# LowerPlumbingBayBoardSchematic.net
KiCad netlist of a schematic drawn in Altium Designer
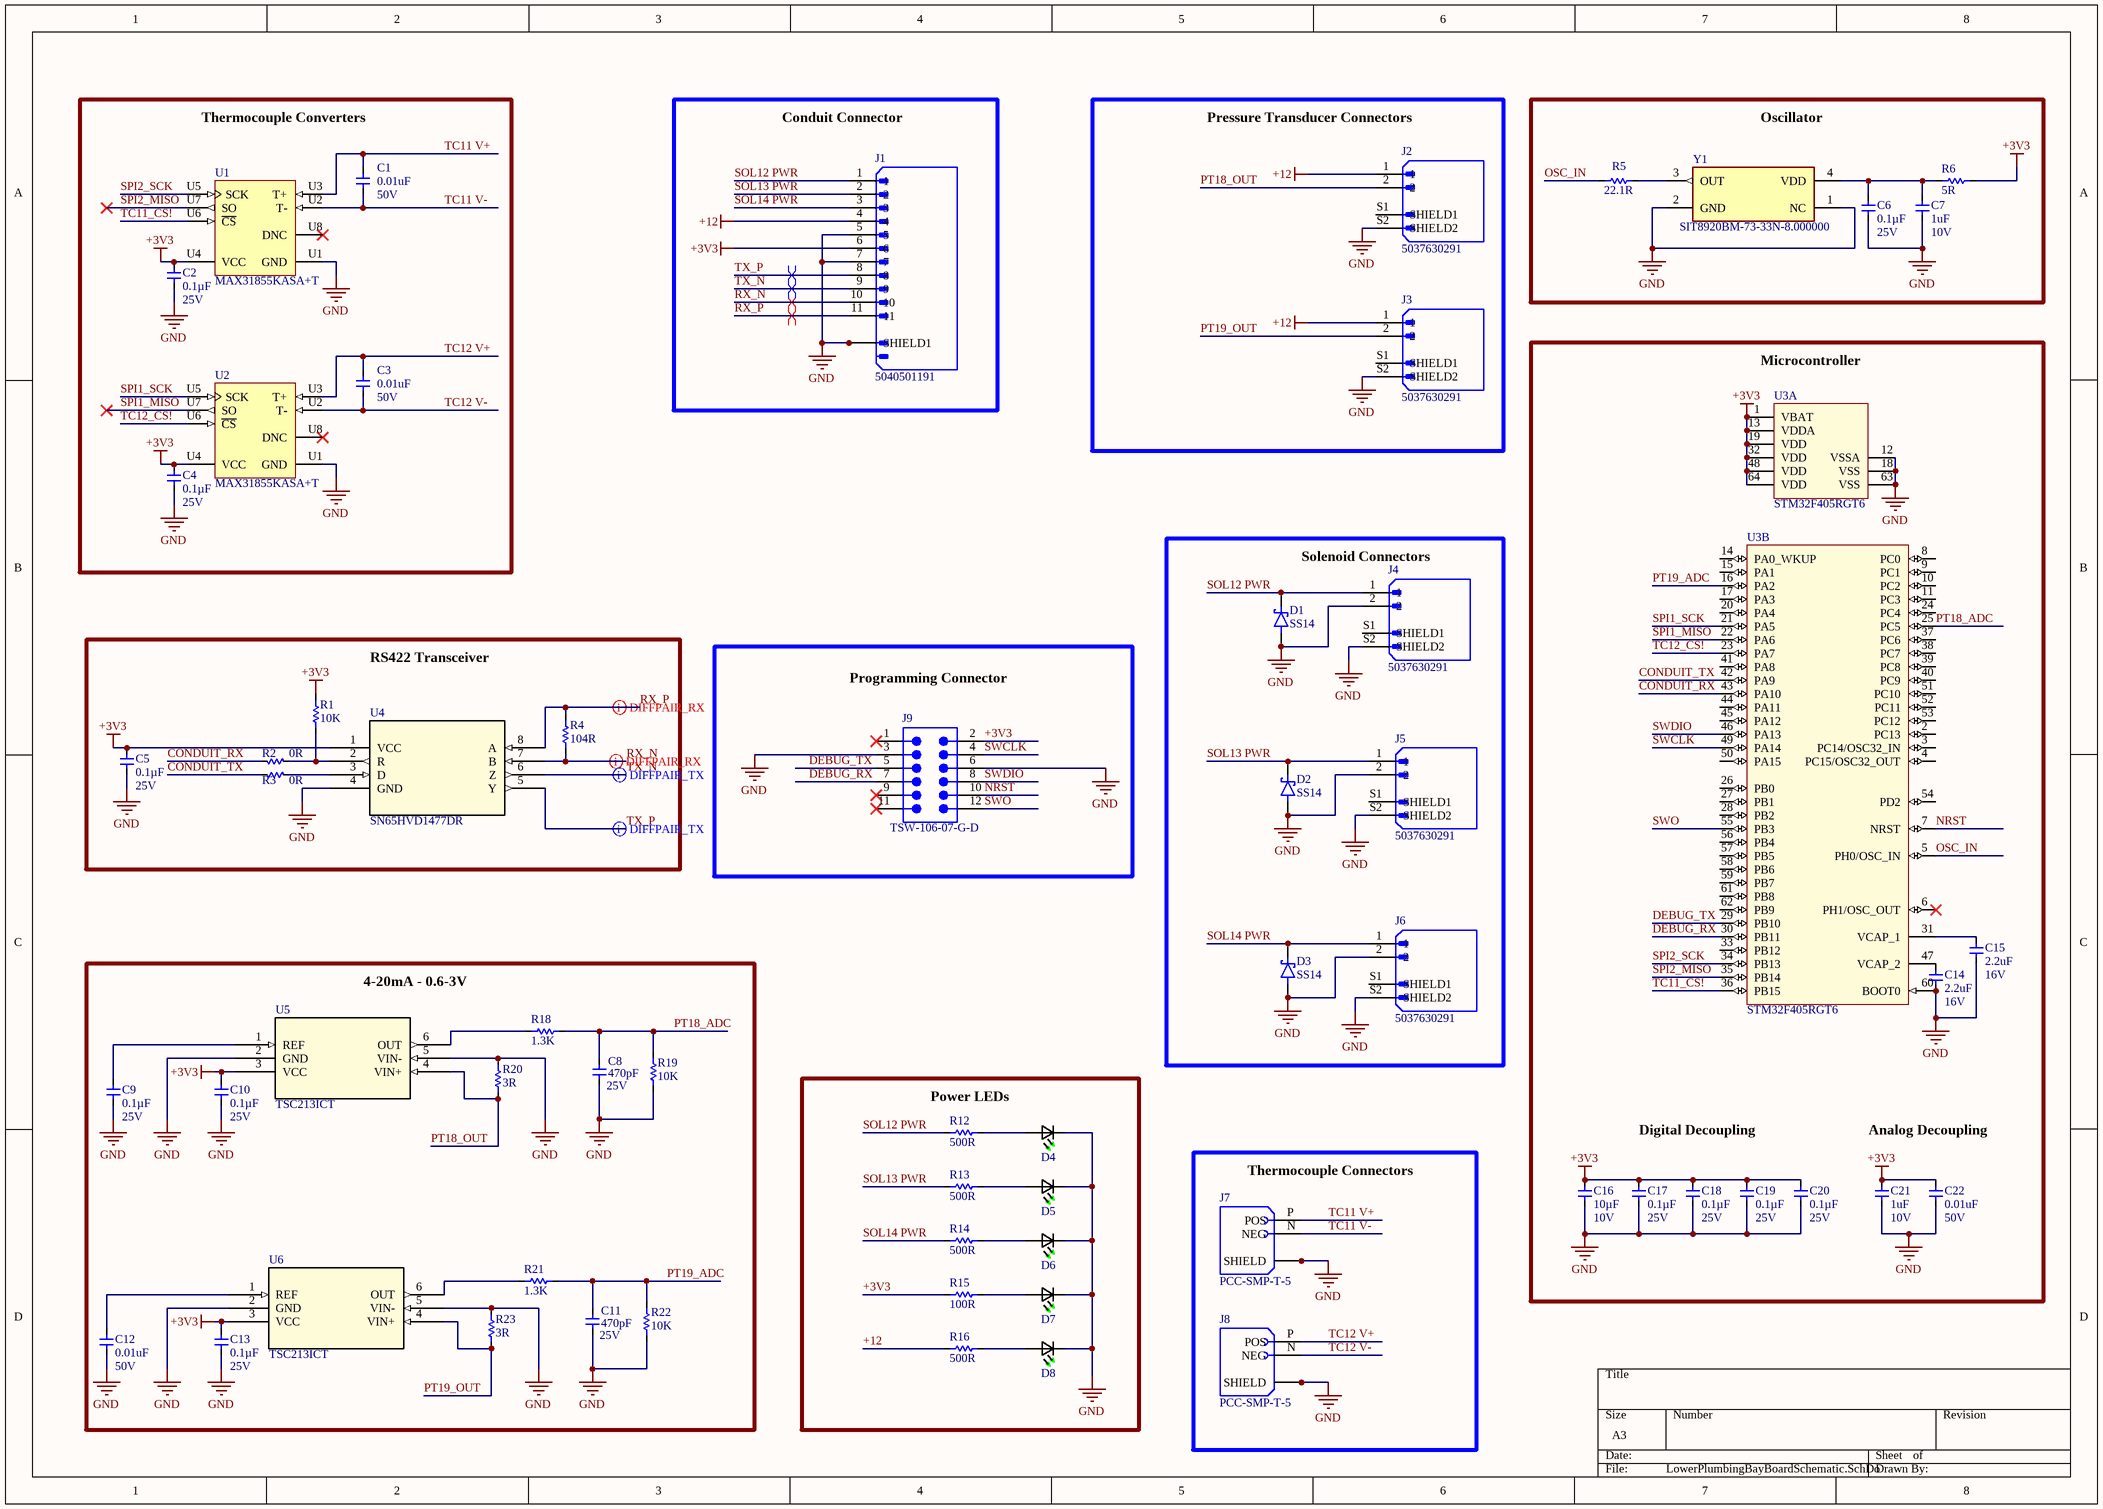
[diagram p0: LowerPlumbingBayBoardSchematic.SchDoc]

(export (version "E")
  (design (tool "Eeschema 10.0.6"))
  (components
    (comp (ref "C1")
      (value "06035A103JAT2A")
      (footprint "0603")
      (description "Multilayer Ceramic Capacitors MLCC - SMD/SMT .01UF 50V 5% 0603")
      (fields
        (field (name "MANUFACTURER") "TDK Corporation")
        (field (name "TOLERANCE") "±10%")
        (field (name "CAPACITANCE") "0.01uF")
        (field (name "VOLTAGE - RATED") "50V")
      )
      (libsource (lib "altium-import") (part "root_2_CGA3E2X7R1H103K080AA_"))
    )
    (comp (ref "C2")
      (value "CGA3E2X7R1E104K080AA")
      (footprint "0603")
      (description "CAP CER 0.1UF 25V X7R 0603")
      (fields
        (field (name "MANUFACTURER") "TDK Corporation")
        (field (name "TOLERANCE") "±10%")
        (field (name "CAPACITANCE") "0.1µF")
        (field (name "VOLTAGE - RATED") "25V")
      )
      (libsource (lib "BioRocketSchematics") (part "CGA3E2X7R1E104K080AA"))
    )
    (comp (ref "C3")
      (value "06035A103JAT2A")
      (footprint "0603")
      (description "Multilayer Ceramic Capacitors MLCC - SMD/SMT .01UF 50V 5% 0603")
      (fields
        (field (name "MANUFACTURER") "TDK Corporation")
        (field (name "TOLERANCE") "±10%")
        (field (name "CAPACITANCE") "0.01uF")
        (field (name "VOLTAGE - RATED") "50V")
      )
      (libsource (lib "altium-import") (part "root_2_CGA3E2X7R1H103K080AA_"))
    )
    (comp (ref "C4")
      (value "CGA3E2X7R1E104K080AA")
      (footprint "0603")
      (description "CAP CER 0.1UF 25V X7R 0603")
      (fields
        (field (name "MANUFACTURER") "TDK Corporation")
        (field (name "TOLERANCE") "±10%")
        (field (name "CAPACITANCE") "0.1µF")
        (field (name "VOLTAGE - RATED") "25V")
      )
      (libsource (lib "BioRocketSchematics") (part "CGA3E2X7R1E104K080AA"))
    )
    (comp (ref "C5")
      (value "CGA3E2X7R1E104K080AA")
      (footprint "0603")
      (description "CAP CER 0.1UF 25V X7R 0603")
      (fields
        (field (name "MANUFACTURER") "TDK Corporation")
        (field (name "TOLERANCE") "±10%")
        (field (name "CAPACITANCE") "0.1µF")
        (field (name "VOLTAGE - RATED") "25V")
      )
      (libsource (lib "BioRocketSchematics") (part "CGA3E2X7R1E104K080AA"))
    )
    (comp (ref "C6")
      (value "CGA3E2X7R1E104K080AA")
      (footprint "0603")
      (description "CAP CER 0.1UF 25V X7R 0603")
      (fields
        (field (name "MANUFACTURER") "TDK Corporation")
        (field (name "TOLERANCE") "±10%")
        (field (name "CAPACITANCE") "0.1µF")
        (field (name "VOLTAGE - RATED") "25V")
      )
      (libsource (lib "") (part "CGA3E2X7R1E104K080AA_1"))
    )
    (comp (ref "C7")
      (value "CL10A105KP8NNNC")
      (footprint "0603")
      (description "CAP CER 1UF 10V X5R 0603")
      (fields
        (field (name "MANUFACTURER") "Samsung Electro-Mechanics")
        (field (name "TOLERANCE") "±10%")
        (field (name "CAPACITANCE") "1uF")
        (field (name "VOLTAGE - RATED") "10V")
      )
      (libsource (lib "") (part "CL10A105KP8NNNC_1"))
    )
    (comp (ref "C8")
      (value "06031C471JAZ2A")
      (footprint "0603")
      (description "Multilayer Ceramic Capacitors MLCC - SMD/SMT 100V 470pF X7R 0603 5% Flex Soft")
      (fields
        (field (name "MANUFACTURER") "TDK Corporation")
        (field (name "TOLERANCE") "±10%")
        (field (name "CAPACITANCE") "470pF")
        (field (name "VOLTAGE - RATED") "25V")
      )
      (libsource (lib "BioRocketSchematics") (part "CGA3E2X7R1E104K080AA"))
    )
    (comp (ref "C9")
      (value "06035A103JAT2A")
      (footprint "0603")
      (description "Multilayer Ceramic Capacitors MLCC - SMD/SMT .01UF 50V 5% 0603")
      (fields
        (field (name "MANUFACTURER") "TDK Corporation")
        (field (name "TOLERANCE") "±10%")
        (field (name "CAPACITANCE") "0.1µF")
        (field (name "VOLTAGE - RATED") "25V")
      )
      (libsource (lib "altium-import") (part "root_2_CGA3E2X7R1E104K080AA_"))
    )
    (comp (ref "C10")
      (value "CGA3E2X7R1E104K080AA")
      (footprint "0603")
      (description "CAP CER 0.1UF 25V X7R 0603")
      (fields
        (field (name "MANUFACTURER") "TDK Corporation")
        (field (name "TOLERANCE") "±10%")
        (field (name "CAPACITANCE") "0.1µF")
        (field (name "VOLTAGE - RATED") "25V")
      )
      (libsource (lib "BioRocketSchematics") (part "CGA3E2X7R1E104K080AA"))
    )
    (comp (ref "C11")
      (value "06031C471JAZ2A")
      (footprint "0603")
      (description "Multilayer Ceramic Capacitors MLCC - SMD/SMT 100V 470pF X7R 0603 5% Flex Soft")
      (fields
        (field (name "MANUFACTURER") "TDK Corporation")
        (field (name "TOLERANCE") "±10%")
        (field (name "CAPACITANCE") "470pF")
        (field (name "VOLTAGE - RATED") "25V")
      )
      (libsource (lib "BioRocketSchematics") (part "CGA3E2X7R1E104K080AA"))
    )
    (comp (ref "C12")
      (value "06035A103JAT2A")
      (footprint "0603")
      (description "Multilayer Ceramic Capacitors MLCC - SMD/SMT .01UF 50V 5% 0603")
      (fields
        (field (name "MANUFACTURER") "TDK Corporation")
        (field (name "TOLERANCE") "±10%")
        (field (name "CAPACITANCE") "0.01uF")
        (field (name "VOLTAGE - RATED") "50V")
      )
      (libsource (lib "altium-import") (part "root_2_CGA3E2X7R1E104K080AA_"))
    )
    (comp (ref "C13")
      (value "CGA3E2X7R1E104K080AA")
      (footprint "0603")
      (description "CAP CER 0.1UF 25V X7R 0603")
      (fields
        (field (name "MANUFACTURER") "TDK Corporation")
        (field (name "TOLERANCE") "±10%")
        (field (name "CAPACITANCE") "0.1µF")
        (field (name "VOLTAGE - RATED") "25V")
      )
      (libsource (lib "BioRocketSchematics") (part "CGA3E2X7R1E104K080AA"))
    )
    (comp (ref "C14")
      (value "C1608X5R1C225K080AB")
      (footprint "0603")
      (description "CAP CER 2.2UF 16V X5R 0603")
      (fields
        (field (name "MANUFACTURER") "TDK Corporation")
        (field (name "TOLERANCE") "±10%")
        (field (name "CAPACITANCE") "2.2uF")
        (field (name "VOLTAGE - RATED") "16V")
      )
      (libsource (lib "BioRocketSchematics") (part "C1608X5R1C225K080AB"))
    )
    (comp (ref "C15")
      (value "C1608X5R1C225K080AB")
      (footprint "0603")
      (description "CAP CER 2.2UF 16V X5R 0603")
      (fields
        (field (name "MANUFACTURER") "TDK Corporation")
        (field (name "TOLERANCE") "±10%")
        (field (name "CAPACITANCE") "2.2uF")
        (field (name "VOLTAGE - RATED") "16V")
      )
      (libsource (lib "BioRocketSchematics") (part "C1608X5R1C225K080AB"))
    )
    (comp (ref "C16")
      (value "CGA3EDX7T1A106M080AU")
      (footprint "0603")
      (description "Multilayer Ceramic Capacitors MLCC - SMD/SMT 0603,X7T,10V,10uF,+/-20%,0.8mm, AEC-Q200")
      (fields
        (field (name "MANUFACTURER") "Samsung Electro-Mechanics")
        (field (name "TOLERANCE") "±20%")
        (field (name "CAPACITANCE") "10µF")
        (field (name "VOLTAGE - RATED") "10V")
      )
      (libsource (lib "BioRocketSchematics") (part "CL10A106MP8NNNC"))
    )
    (comp (ref "C17")
      (value "CGA3E2X7R1E104K080AA")
      (footprint "0603")
      (description "CAP CER 0.1UF 25V X7R 0603")
      (fields
        (field (name "MANUFACTURER") "TDK Corporation")
        (field (name "TOLERANCE") "±10%")
        (field (name "CAPACITANCE") "0.1µF")
        (field (name "VOLTAGE - RATED") "25V")
      )
      (libsource (lib "BioRocketSchematics") (part "CGA3E2X7R1E104K080AA"))
    )
    (comp (ref "C18")
      (value "CGA3E2X7R1E104K080AA")
      (footprint "0603")
      (description "CAP CER 0.1UF 25V X7R 0603")
      (fields
        (field (name "MANUFACTURER") "TDK Corporation")
        (field (name "TOLERANCE") "±10%")
        (field (name "CAPACITANCE") "0.1µF")
        (field (name "VOLTAGE - RATED") "25V")
      )
      (libsource (lib "BioRocketSchematics") (part "CGA3E2X7R1E104K080AA"))
    )
    (comp (ref "C19")
      (value "CGA3E2X7R1E104K080AA")
      (footprint "0603")
      (description "CAP CER 0.1UF 25V X7R 0603")
      (fields
        (field (name "MANUFACTURER") "TDK Corporation")
        (field (name "TOLERANCE") "±10%")
        (field (name "CAPACITANCE") "0.1µF")
        (field (name "VOLTAGE - RATED") "25V")
      )
      (libsource (lib "BioRocketSchematics") (part "CGA3E2X7R1E104K080AA"))
    )
    (comp (ref "C20")
      (value "CGA3E2X7R1E104K080AA")
      (footprint "0603")
      (description "CAP CER 0.1UF 25V X7R 0603")
      (fields
        (field (name "MANUFACTURER") "TDK Corporation")
        (field (name "TOLERANCE") "±10%")
        (field (name "CAPACITANCE") "0.1µF")
        (field (name "VOLTAGE - RATED") "25V")
      )
      (libsource (lib "BioRocketSchematics") (part "CGA3E2X7R1E104K080AA"))
    )
    (comp (ref "C21")
      (value "CL10A105KP8NNNC")
      (footprint "0603")
      (description "CAP CER 1UF 10V X5R 0603")
      (fields
        (field (name "MANUFACTURER") "Samsung Electro-Mechanics")
        (field (name "TOLERANCE") "±10%")
        (field (name "CAPACITANCE") "1uF")
        (field (name "VOLTAGE - RATED") "10V")
      )
      (libsource (lib "BioRocketSchematics") (part "CL10A105KP8NNNC"))
    )
    (comp (ref "C22")
      (value "06035A103JAT2A")
      (footprint "0603")
      (description "Multilayer Ceramic Capacitors MLCC - SMD/SMT .01UF 50V 5% 0603")
      (fields
        (field (name "MANUFACTURER") "TDK Corporation")
        (field (name "TOLERANCE") "±10%")
        (field (name "CAPACITANCE") "0.01uF")
        (field (name "VOLTAGE - RATED") "50V")
      )
      (libsource (lib "altium-import") (part "root_2_CGA3E2X7R1H103K080AA_"))
    )
    (comp (ref "D1")
      (value "SS14")
      (footprint "DIOM4325X250N")
      (description "Schottky Diodes & Rectifiers SMA 40V 1.0A")
      (libsource (lib "BioRocketSchematics") (part "SS14"))
    )
    (comp (ref "D2")
      (value "SS14")
      (footprint "DIOM4325X250N")
      (description "Schottky Diodes & Rectifiers SMA 40V 1.0A")
      (libsource (lib "BioRocketSchematics") (part "SS14"))
    )
    (comp (ref "D3")
      (value "SS14")
      (footprint "DIOM4325X250N")
      (description "Schottky Diodes & Rectifiers SMA 40V 1.0A")
      (libsource (lib "BioRocketSchematics") (part "SS14"))
    )
    (comp (ref "D4")
      (value "LTST-C191KGKT")
      (footprint "LTST-C191KGKT")
      (description "LED,  LTST-C191KGKT")
      (fields (field (name "MANUFACTURER") "Vishay Lite-On"))
      (libsource (lib "BioRocketSchematics") (part "LTST-C191KGKT"))
    )
    (comp (ref "D5")
      (value "LTST-C191KGKT")
      (footprint "LTST-C191KGKT")
      (description "LED,  LTST-C191KGKT")
      (fields (field (name "MANUFACTURER") "Vishay Lite-On"))
      (libsource (lib "BioRocketSchematics") (part "LTST-C191KGKT"))
    )
    (comp (ref "D6")
      (value "LTST-C191KGKT")
      (footprint "LTST-C191KGKT")
      (description "LED,  LTST-C191KGKT")
      (fields (field (name "MANUFACTURER") "Vishay Lite-On"))
      (libsource (lib "BioRocketSchematics") (part "LTST-C191KGKT"))
    )
    (comp (ref "D7")
      (value "LTST-C191KGKT")
      (footprint "LTST-C191KGKT")
      (description "LED,  LTST-C191KGKT")
      (fields (field (name "MANUFACTURER") "Vishay Lite-On"))
      (libsource (lib "BioRocketSchematics") (part "LTST-C191KGKT"))
    )
    (comp (ref "D8")
      (value "LTST-C191KGKT")
      (footprint "LTST-C191KGKT")
      (description "LED,  LTST-C191KGKT")
      (fields (field (name "MANUFACTURER") "Vishay Lite-On"))
      (libsource (lib "BioRocketSchematics") (part "LTST-C191KGKT"))
    )
    (comp (ref "J1")
      (value "5040501191")
      (footprint "MOLEX_5040501191")
      (description "Headers & Wire Housings 1.5MM PicoLock SMT HDR RA POS SDLCK 11P")
      (libsource (lib "BioRocketSchematics") (part "5040501191"))
    )
    (comp (ref "J2")
      (value "5037630291")
      (footprint "2MOLEX_5037630291")
      (description "Headers & Wire Housings PicoLock 1.0 WB Plg R/A 2Ckt Pos SideLk")
      (libsource (lib "BioRocketSchematics") (part "5037630291"))
    )
    (comp (ref "J3")
      (value "5037630291")
      (footprint "2MOLEX_5037630291")
      (description "Headers & Wire Housings PicoLock 1.0 WB Plg R/A 2Ckt Pos SideLk")
      (libsource (lib "BioRocketSchematics") (part "5037630291"))
    )
    (comp (ref "J4")
      (value "5037630291")
      (footprint "2MOLEX_5037630291")
      (description "Headers & Wire Housings PicoLock 1.0 WB Plg R/A 2Ckt Pos SideLk")
      (libsource (lib "BioRocketSchematics") (part "5037630291"))
    )
    (comp (ref "J5")
      (value "5037630291")
      (footprint "2MOLEX_5037630291")
      (description "Headers & Wire Housings PicoLock 1.0 WB Plg R/A 2Ckt Pos SideLk")
      (libsource (lib "BioRocketSchematics") (part "5037630291"))
    )
    (comp (ref "J6")
      (value "5037630291")
      (footprint "2MOLEX_5037630291")
      (description "Headers & Wire Housings PicoLock 1.0 WB Plg R/A 2Ckt Pos SideLk")
      (libsource (lib "BioRocketSchematics") (part "5037630291"))
    )
    (comp (ref "J7")
      (value "PCC-SMP-T-5")
      (footprint "OMEGA_PCC-SMP-K-5")
      (description "Thermocouple Connector, Circuit Board, Socket, Type T, Miniature, PCC SMP Series")
      (fields (field (name "MP") "PCC-SMP-K-5") (field (name "MF") "Omega Engineering"))
      (libsource (lib "BioRocketSchematics") (part "PCC-SMP-K-5"))
    )
    (comp (ref "J8")
      (value "PCC-SMP-T-5")
      (footprint "OMEGA_PCC-SMP-K-5")
      (description "Thermocouple Connector, Circuit Board, Socket, Type T, Miniature, PCC SMP Series")
      (fields (field (name "MP") "PCC-SMP-K-5") (field (name "MF") "Omega Engineering"))
      (libsource (lib "BioRocketSchematics") (part "PCC-SMP-K-5"))
    )
    (comp (ref "J9")
      (value "TSW-106-07-G-D")
      (footprint "SMTC-TSW-106-07-X-D")
      (description "0.025\" SQ Post Header, Through-hole, Vertical, -55 to 125 degC, 2.54 mm Pitch, 12-Pin, Male, RoHS")
      (fields (field (name "MANUFACTURER") "Samtec"))
      (libsource (lib "BioRocketSchematics") (part "SMTC-TSW-106-07-X-D_1"))
    )
    (comp (ref "R1")
      (value "ERJ-3GEYJ103V")
      (footprint "0603")
      (description "SMD Chip Resistor, 10 kOhm, ï¿½ 5%, 100 mW, 0603 [1608 Metric], Thick Film, General Purpose")
      (fields
        (field (name "TOLERANCE") "±5%")
        (field (name "MANUFACTURER") "Panasonic Electronic Components")
        (field (name "RESISTANCE") "10K")
      )
      (libsource (lib "BioRocketSchematics") (part "ERJ-3GEYJ103V"))
    )
    (comp (ref "R2")
      (value "0R")
      (footprint "0603")
      (description "RES SMD 0 OHM 1% JUMPER 1/10W 0603")
      (fields
        (field (name "DISTRIBUTOR PART #") "RMCF0603ZT0R00CT-ND")
        (field (name "MANUFACTURER") "Stackpole Electronics Inc")
      )
      (libsource (lib "BioRocketSchematics") (part "RT-0R00-F-1/10W-0603"))
    )
    (comp (ref "R3")
      (value "0R")
      (footprint "0603")
      (description "RES SMD 0 OHM 1% JUMPER 1/10W 0603")
      (fields
        (field (name "DISTRIBUTOR PART #") "RMCF0603ZT0R00CT-ND")
        (field (name "MANUFACTURER") "Stackpole Electronics Inc")
      )
      (libsource (lib "BioRocketSchematics") (part "RT-0R00-F-1/10W-0603"))
    )
    (comp (ref "R4")
      (value "RN73H1JTTD1040D25")
      (footprint "0603")
      (description "Thin Film Resistors - SMD 104Ohm,0603,0.5%,25p")
      (fields
        (field (name "TOLERANCE") "±5%")
        (field (name "MANUFACTURER") "Panasonic Electronic Components")
        (field (name "RESISTANCE") "104R")
      )
      (libsource (lib "BioRocketSchematics") (part "ERJ-3GEYJ103V"))
    )
    (comp (ref "R5")
      (value "ERJ-P03F22R1V")
      (footprint "0603")
      (description "Thick Film Resistors - SMD 0603 22.1ohms 0.2W 1% AEC-Q200")
      (fields
        (field (name "MANUFACTURER") "Panasonic")
        (field (name "MANUFACTURER PART NUMBER") "ERJ-3EKF38R3V")
        (field (name "RESISTANCE") "22.1R")
      )
      (libsource (lib "BioRocketSchematics") (part "ERJ-3EKF38R3V"))
    )
    (comp (ref "R6")
      (value "PWR2010W5R00JE")
      (footprint "BO_PWR2010")
      (description "Res Wirewound 2010 5 Ohm 5% 1/2W ±50ppm/°C Molded SMD SMD T/R")
      (fields
        (field (name "MANUFACTURER") "Bourns")
        (field (name "TOLERANCE") "5%")
        (field (name "RESISTANCE") "5R")
      )
      (libsource (lib "BioRocketSchematics") (part "PWR2010W5R00JE"))
    )
    (comp (ref "R12")
      (value "RT0603BRC07500RL")
      (footprint "0603")
      (description "Thin Film Resistors - SMD 500 ohm 0.1% 15ppm H igh Stability")
      (fields
        (field (name "MANUFACTURER") "Yageo")
        (field (name "MANUFACTURER PART NUMBER") "RC0603FR-071KL")
        (field (name "RESISTANCE") "500R")
      )
      (libsource (lib "BioRocketSchematics") (part "RC0603FR-071KL"))
    )
    (comp (ref "R13")
      (value "RT0603BRC07500RL")
      (footprint "0603")
      (description "Thin Film Resistors - SMD 500 ohm 0.1% 15ppm H igh Stability")
      (fields
        (field (name "MANUFACTURER") "Yageo")
        (field (name "MANUFACTURER PART NUMBER") "RC0603FR-071KL")
        (field (name "RESISTANCE") "500R")
      )
      (libsource (lib "BioRocketSchematics") (part "RC0603FR-071KL"))
    )
    (comp (ref "R14")
      (value "RT0603BRC07500RL")
      (footprint "0603")
      (description "Thin Film Resistors - SMD 500 ohm 0.1% 15ppm H igh Stability")
      (fields
        (field (name "MANUFACTURER") "Yageo")
        (field (name "MANUFACTURER PART NUMBER") "RC0603FR-071KL")
        (field (name "RESISTANCE") "500R")
      )
      (libsource (lib "BioRocketSchematics") (part "RC0603FR-071KL"))
    )
    (comp (ref "R15")
      (value "ERJ-P03F1000V")
      (footprint "0603")
      (description "Thick Film Resistors - SMD 0603 100ohms 0.2W 1% AEC-Q200")
      (fields
        (field (name "MANUFACTURER") "TE Connectivity")
        (field (name "MANUFACTURER PART NUMBER") "CRGCQ0402J330R")
        (field (name "RESISTANCE") "100R")
      )
      (libsource (lib "BioRocketSchematics") (part "CRGCQ0402J330R"))
    )
    (comp (ref "R16")
      (value "RT0603BRC07500RL")
      (footprint "0603")
      (description "Thin Film Resistors - SMD 500 ohm 0.1% 15ppm H igh Stability")
      (fields
        (field (name "MANUFACTURER") "Yageo")
        (field (name "MANUFACTURER PART NUMBER") "RC0603FR-071KL")
        (field (name "RESISTANCE") "500R")
      )
      (libsource (lib "BioRocketSchematics") (part "RC0603FR-071KL"))
    )
    (comp (ref "R18")
      (value "ERJ-H3EF1301V")
      (footprint "0603")
      (description "Thick Film Resistors - SMD 0603 1.3KOhm 1% AEC-Q200")
      (fields
        (field (name "MANUFACTURER") "Bourns")
        (field (name "MANUFACTURER PART NUMBER") "PWR2010W5R00JE")
        (field (name "RESISTANCE") "1.3K")
      )
      (libsource (lib "BioRocketSchematics") (part "PWR2010W5R00JE"))
    )
    (comp (ref "R19")
      (value "ERJ-3GEYJ103V")
      (footprint "0603")
      (description "SMD Chip Resistor, 10 kOhm, ï¿½ 5%, 100 mW, 0603 [1608 Metric], Thick Film, General Purpose")
      (fields
        (field (name "TOLERANCE") "±5%")
        (field (name "MANUFACTURER") "Panasonic Electronic Components")
        (field (name "RESISTANCE") "10K")
      )
      (libsource (lib "BioRocketSchematics") (part "ERJ-3GEYJ103V"))
    )
    (comp (ref "R20")
      (value "ERJ-3RQF3R0V")
      (footprint "0603")
      (description "Current Sense Resistors - SMD 0603 3.0ohm 1% Curr Sense AEC-Q200")
      (fields
        (field (name "TOLERANCE") "±5%")
        (field (name "MANUFACTURER") "Panasonic Electronic Components")
        (field (name "RESISTANCE") "3R")
      )
      (libsource (lib "BioRocketSchematics") (part "ERJ-3GEYJ103V"))
    )
    (comp (ref "R21")
      (value "ERJ-H3EF1301V")
      (footprint "0603")
      (description "Thick Film Resistors - SMD 0603 1.3KOhm 1% AEC-Q200")
      (fields
        (field (name "MANUFACTURER") "Bourns")
        (field (name "MANUFACTURER PART NUMBER") "PWR2010W5R00JE")
        (field (name "RESISTANCE") "1.3K")
      )
      (libsource (lib "BioRocketSchematics") (part "PWR2010W5R00JE"))
    )
    (comp (ref "R22")
      (value "ERJ-3GEYJ103V")
      (footprint "0603")
      (description "SMD Chip Resistor, 10 kOhm, ï¿½ 5%, 100 mW, 0603 [1608 Metric], Thick Film, General Purpose")
      (fields
        (field (name "TOLERANCE") "±5%")
        (field (name "MANUFACTURER") "Panasonic Electronic Components")
        (field (name "RESISTANCE") "10K")
      )
      (libsource (lib "BioRocketSchematics") (part "ERJ-3GEYJ103V"))
    )
    (comp (ref "R23")
      (value "ERJ-3RQF3R0V")
      (footprint "0603")
      (description "Current Sense Resistors - SMD 0603 3.0ohm 1% Curr Sense AEC-Q200")
      (fields
        (field (name "TOLERANCE") "±5%")
        (field (name "MANUFACTURER") "Panasonic Electronic Components")
        (field (name "RESISTANCE") "3R")
      )
      (libsource (lib "BioRocketSchematics") (part "ERJ-3GEYJ103V"))
    )
    (comp (ref "U1")
      (value "MAX31855KASA+T")
      (footprint "MAXM-S8+4_L")
      (fields (field (name "GENERIC PART NUMBER") "MAX31855"))
      (libsource (lib "BioRocketSchematics") (part "MAX31855-S8+4_1"))
    )
    (comp (ref "U2")
      (value "MAX31855KASA+T")
      (footprint "MAXM-S8+4_L")
      (fields (field (name "GENERIC PART NUMBER") "MAX31855"))
      (libsource (lib "BioRocketSchematics") (part "MAX31855-S8+4_1"))
    )
    (comp (ref "U3")
      (value "STM32F405RGT6")
      (footprint "STM-LQFP64_L")
      (description "IC MCU 32BIT 1MB FLASH 64LQFP")
      (fields (field (name "MANUFACTURER") "STMicroelectronics"))
      (libsource (lib "PlumBay_SchLib") (part "STM32F405RGT6"))
    )
    (comp (ref "U4")
      (value "SN65HVD1477DR")
      (footprint "D8_TEX")
      (description "3.3V, Full-Duplex RS-485, 16kV IEC ESD, 50Mbps data rate, No Enables 8-SOIC -40 to 125")
      (fields (field (name "COPYRIGHT") "Copyright (C) 2022 Ultra Librarian. All rights reserved."))
      (libsource (lib "BioRocketSchematics") (part "SN65HVD1477DR"))
    )
    (comp (ref "U5")
      (value "TSC213ICT")
      (footprint "SC70-6_STM")
      (description "No Description Available")
      (libsource (lib "BioRocketSchematics") (part "TSC213ICT"))
    )
    (comp (ref "U6")
      (value "TSC213ICT")
      (footprint "SC70-6_STM")
      (description "No Description Available")
      (libsource (lib "BioRocketSchematics") (part "TSC213ICT"))
    )
    (comp (ref "Y1")
      (value "SIT8920BM-73-33N-8.000000")
      (footprint "FP-SIT8920BM-73-33N-8_000-MFG")
      (description "MEMS OSC XO 8.0000MHZ LVCM LVTTL")
      (libsource (lib "Altium Content Vault") (part "f8eed742da43ac8d7009b5f8d825914"))
    )
  )
  (nets
    (net (code "1") (name "+3V3") (class "Default")
      (node (ref "C10") (pin "1") (pinfunction "1_1") (pintype "passive"))
      (node (ref "C13") (pin "1") (pinfunction "1_1") (pintype "passive"))
      (node (ref "C16") (pin "1") (pinfunction "1_1") (pintype "passive"))
      (node (ref "C17") (pin "1") (pinfunction "1_1") (pintype "passive"))
      (node (ref "C18") (pin "1") (pinfunction "1_1") (pintype "passive"))
      (node (ref "C19") (pin "1") (pinfunction "1_1") (pintype "passive"))
      (node (ref "C2") (pin "1") (pinfunction "1_1") (pintype "passive"))
      (node (ref "C20") (pin "1") (pinfunction "1_1") (pintype "passive"))
      (node (ref "C21") (pin "1") (pinfunction "1_1") (pintype "passive"))
      (node (ref "C22") (pin "1") (pinfunction "1_1") (pintype "passive"))
      (node (ref "C4") (pin "1") (pinfunction "1_1") (pintype "passive"))
      (node (ref "C5") (pin "1") (pinfunction "1_1") (pintype "passive"))
      (node (ref "J1") (pin "6") (pinfunction "6_6") (pintype "passive"))
      (node (ref "J9") (pin "2") (pinfunction "2_2") (pintype "passive"))
      (node (ref "R1") (pin "2") (pinfunction "2_2") (pintype "passive"))
      (node (ref "R15") (pin "1") (pinfunction "1_1") (pintype "passive"))
      (node (ref "R6") (pin "2") (pinfunction "2_2") (pintype "passive"))
      (node (ref "U1") (pin "U4") (pinfunction "VCC_U4") (pintype "power_in"))
      (node (ref "U2") (pin "U4") (pinfunction "VCC_U4") (pintype "power_in"))
      (node (ref "U3") (pin "1") (pinfunction "VBAT_1") (pintype "power_in"))
      (node (ref "U3") (pin "13") (pinfunction "VDDA_13") (pintype "power_in"))
      (node (ref "U3") (pin "19") (pinfunction "VDD_19") (pintype "power_in"))
      (node (ref "U3") (pin "32") (pinfunction "VDD_32") (pintype "power_in"))
      (node (ref "U3") (pin "48") (pinfunction "VDD_48") (pintype "power_in"))
      (node (ref "U3") (pin "64") (pinfunction "VDD_64") (pintype "power_in"))
      (node (ref "U4") (pin "1") (pinfunction "VCC_1") (pintype "power_in"))
      (node (ref "U5") (pin "3") (pinfunction "VCC_3") (pintype "power_in"))
      (node (ref "U6") (pin "3") (pinfunction "VCC_3") (pintype "power_in"))
    )
    (net (code "2") (name "+12") (class "Default")
      (node (ref "J1") (pin "4") (pinfunction "4_4") (pintype "passive"))
      (node (ref "J2") (pin "1") (pinfunction "1_1") (pintype "passive"))
      (node (ref "J3") (pin "1") (pinfunction "1_1") (pintype "passive"))
      (node (ref "R16") (pin "1") (pinfunction "1_1") (pintype "passive"))
    )
    (net (code "3") (name "/CONDUIT_RX") (class "Default")
      (node (ref "R2") (pin "1") (pintype "passive"))
      (node (ref "U3") (pin "43") (pinfunction "PA10_43") (pintype "bidirectional"))
    )
    (net (code "4") (name "/CONDUIT_TX") (class "Default")
      (node (ref "R3") (pin "1") (pintype "passive"))
      (node (ref "U3") (pin "42") (pinfunction "PA9_42") (pintype "bidirectional"))
    )
    (net (code "5") (name "/DEBUG_RX") (class "Default")
      (node (ref "J9") (pin "7") (pinfunction "7_7") (pintype "passive"))
      (node (ref "U3") (pin "30") (pinfunction "PB11_30") (pintype "bidirectional"))
    )
    (net (code "6") (name "/DEBUG_TX") (class "Default")
      (node (ref "J9") (pin "5") (pinfunction "5_5") (pintype "passive"))
      (node (ref "U3") (pin "29") (pinfunction "PB10_29") (pintype "bidirectional"))
    )
    (net (code "7") (name "/NRST") (class "Default")
      (node (ref "J9") (pin "10") (pinfunction "10_10") (pintype "passive"))
      (node (ref "U3") (pin "7") (pinfunction "NRST_7") (pintype "bidirectional"))
    )
    (net (code "8") (name "/OSC_IN") (class "Default")
      (node (ref "R5") (pin "1") (pinfunction "1_1") (pintype "passive"))
      (node (ref "U3") (pin "5") (pinfunction "PH0/OSC_IN_5") (pintype "bidirectional"))
    )
    (net (code "9") (name "/PT18_ADC") (class "Default")
      (node (ref "C8") (pin "1") (pinfunction "1_1") (pintype "passive"))
      (node (ref "R18") (pin "2") (pinfunction "2_2") (pintype "passive"))
      (node (ref "R19") (pin "2") (pinfunction "2_2") (pintype "passive"))
      (node (ref "U3") (pin "25") (pinfunction "PC5_25") (pintype "bidirectional"))
    )
    (net (code "10") (name "/PT18_OUT") (class "Default")
      (node (ref "J2") (pin "2") (pinfunction "2_2") (pintype "passive"))
      (node (ref "R20") (pin "1") (pinfunction "1_1") (pintype "passive"))
      (node (ref "U5") (pin "4") (pinfunction "VIN+_4") (pintype "input"))
    )
    (net (code "11") (name "/PT19_ADC") (class "Default")
      (node (ref "C11") (pin "1") (pinfunction "1_1") (pintype "passive"))
      (node (ref "R21") (pin "2") (pinfunction "2_2") (pintype "passive"))
      (node (ref "R22") (pin "2") (pinfunction "2_2") (pintype "passive"))
      (node (ref "U3") (pin "16") (pinfunction "PA2_16") (pintype "bidirectional"))
    )
    (net (code "12") (name "/PT19_OUT") (class "Default")
      (node (ref "J3") (pin "2") (pinfunction "2_2") (pintype "passive"))
      (node (ref "R23") (pin "1") (pinfunction "1_1") (pintype "passive"))
      (node (ref "U6") (pin "4") (pinfunction "VIN+_4") (pintype "input"))
    )
    (net (code "13") (name "/RX_N") (class "Default")
      (node (ref "J1") (pin "10") (pinfunction "10_10") (pintype "passive"))
      (node (ref "R4") (pin "1") (pinfunction "1_1") (pintype "passive"))
      (node (ref "U4") (pin "7") (pinfunction "B_7") (pintype "input"))
    )
    (net (code "14") (name "/RX_P") (class "Default")
      (node (ref "J1") (pin "11") (pinfunction "11_11") (pintype "passive"))
      (node (ref "R4") (pin "2") (pinfunction "2_2") (pintype "passive"))
      (node (ref "U4") (pin "8") (pinfunction "A_8") (pintype "input"))
    )
    (net (code "15") (name "/SOL12 PWR") (class "Default")
      (node (ref "D1") (pin "C") (pinfunction "K_C") (pintype "passive"))
      (node (ref "J1") (pin "1") (pinfunction "1_1") (pintype "passive"))
      (node (ref "J4") (pin "1") (pinfunction "1_1") (pintype "passive"))
      (node (ref "R12") (pin "1") (pinfunction "1_1") (pintype "passive"))
    )
    (net (code "16") (name "/SOL13 PWR") (class "Default")
      (node (ref "D2") (pin "C") (pinfunction "K_C") (pintype "passive"))
      (node (ref "J1") (pin "2") (pinfunction "2_2") (pintype "passive"))
      (node (ref "J5") (pin "1") (pinfunction "1_1") (pintype "passive"))
      (node (ref "R13") (pin "1") (pinfunction "1_1") (pintype "passive"))
    )
    (net (code "17") (name "/SOL14 PWR") (class "Default")
      (node (ref "D3") (pin "C") (pinfunction "K_C") (pintype "passive"))
      (node (ref "J1") (pin "3") (pinfunction "3_3") (pintype "passive"))
      (node (ref "J6") (pin "1") (pinfunction "1_1") (pintype "passive"))
      (node (ref "R14") (pin "1") (pinfunction "1_1") (pintype "passive"))
    )
    (net (code "18") (name "/SPI1_MISO") (class "Default")
      (node (ref "U2") (pin "U7") (pinfunction "SO_U7") (pintype "output"))
      (node (ref "U3") (pin "22") (pinfunction "PA6_22") (pintype "bidirectional"))
    )
    (net (code "19") (name "/SPI1_SCK") (class "Default")
      (node (ref "U2") (pin "U5") (pinfunction "SCK_U5") (pintype "input"))
      (node (ref "U3") (pin "21") (pinfunction "PA5_21") (pintype "bidirectional"))
    )
    (net (code "20") (name "/SPI2_MISO") (class "Default")
      (node (ref "U1") (pin "U7") (pinfunction "SO_U7") (pintype "output"))
      (node (ref "U3") (pin "35") (pinfunction "PB14_35") (pintype "bidirectional"))
    )
    (net (code "21") (name "/SPI2_SCK") (class "Default")
      (node (ref "U1") (pin "U5") (pinfunction "SCK_U5") (pintype "input"))
      (node (ref "U3") (pin "34") (pinfunction "PB13_34") (pintype "bidirectional"))
    )
    (net (code "22") (name "/SWCLK") (class "Default")
      (node (ref "J9") (pin "4") (pinfunction "4_4") (pintype "passive"))
      (node (ref "U3") (pin "49") (pinfunction "PA14_49") (pintype "bidirectional"))
    )
    (net (code "23") (name "/SWDIO") (class "Default")
      (node (ref "J9") (pin "8") (pinfunction "8_8") (pintype "passive"))
      (node (ref "U3") (pin "46") (pinfunction "PA13_46") (pintype "bidirectional"))
    )
    (net (code "24") (name "/SWO") (class "Default")
      (node (ref "J9") (pin "12") (pinfunction "12_12") (pintype "passive"))
      (node (ref "U3") (pin "55") (pinfunction "PB3_55") (pintype "bidirectional"))
    )
    (net (code "25") (name "/TC11 V+") (class "Default")
      (node (ref "C1") (pin "1") (pinfunction "1_1") (pintype "passive"))
      (node (ref "J7") (pin "P") (pinfunction "POS_P") (pintype "passive"))
      (node (ref "U1") (pin "U3") (pinfunction "T+_U3") (pintype "input"))
    )
    (net (code "26") (name "/TC11 V-") (class "Default")
      (node (ref "C1") (pin "2") (pinfunction "2_2") (pintype "passive"))
      (node (ref "J7") (pin "N") (pinfunction "NEG_N") (pintype "passive"))
      (node (ref "U1") (pin "U2") (pinfunction "T-_U2") (pintype "input"))
    )
    (net (code "27") (name "/TC11_CS!") (class "Default")
      (node (ref "U1") (pin "U6") (pinfunction "~{CS}_U6") (pintype "input"))
      (node (ref "U3") (pin "36") (pinfunction "PB15_36") (pintype "bidirectional"))
    )
    (net (code "28") (name "/TC12 V+") (class "Default")
      (node (ref "C3") (pin "1") (pinfunction "1_1") (pintype "passive"))
      (node (ref "J8") (pin "P") (pinfunction "POS_P") (pintype "passive"))
      (node (ref "U2") (pin "U3") (pinfunction "T+_U3") (pintype "input"))
    )
    (net (code "29") (name "/TC12 V-") (class "Default")
      (node (ref "C3") (pin "2") (pinfunction "2_2") (pintype "passive"))
      (node (ref "J8") (pin "N") (pinfunction "NEG_N") (pintype "passive"))
      (node (ref "U2") (pin "U2") (pinfunction "T-_U2") (pintype "input"))
    )
    (net (code "30") (name "/TC12_CS!") (class "Default")
      (node (ref "U2") (pin "U6") (pinfunction "~{CS}_U6") (pintype "input"))
      (node (ref "U3") (pin "23") (pinfunction "PA7_23") (pintype "bidirectional"))
    )
    (net (code "31") (name "/TX_N") (class "Default")
      (node (ref "J1") (pin "9") (pinfunction "9_9") (pintype "passive"))
      (node (ref "U4") (pin "6") (pinfunction "Z_6") (pintype "output"))
    )
    (net (code "32") (name "/TX_P") (class "Default")
      (node (ref "J1") (pin "8") (pinfunction "8_8") (pintype "passive"))
      (node (ref "U4") (pin "5") (pinfunction "Y_5") (pintype "output"))
    )
    (net (code "33") (name "GND") (class "Default")
      (node (ref "C10") (pin "2") (pinfunction "2_2") (pintype "passive"))
      (node (ref "C11") (pin "2") (pinfunction "2_2") (pintype "passive"))
      (node (ref "C12") (pin "2") (pinfunction "2_2") (pintype "passive"))
      (node (ref "C13") (pin "2") (pinfunction "2_2") (pintype "passive"))
      (node (ref "C14") (pin "2") (pinfunction "2_2") (pintype "passive"))
      (node (ref "C15") (pin "1") (pinfunction "1_1") (pintype "passive"))
      (node (ref "C16") (pin "2") (pinfunction "2_2") (pintype "passive"))
      (node (ref "C17") (pin "2") (pinfunction "2_2") (pintype "passive"))
      (node (ref "C18") (pin "2") (pinfunction "2_2") (pintype "passive"))
      (node (ref "C19") (pin "2") (pinfunction "2_2") (pintype "passive"))
      (node (ref "C2") (pin "2") (pinfunction "2_2") (pintype "passive"))
      (node (ref "C20") (pin "2") (pinfunction "2_2") (pintype "passive"))
      (node (ref "C21") (pin "2") (pinfunction "2_2") (pintype "passive"))
      (node (ref "C22") (pin "2") (pinfunction "2_2") (pintype "passive"))
      (node (ref "C4") (pin "2") (pinfunction "2_2") (pintype "passive"))
      (node (ref "C5") (pin "2") (pinfunction "2_2") (pintype "passive"))
      (node (ref "C6") (pin "1") (pinfunction "1_1") (pintype "passive"))
      (node (ref "C7") (pin "1") (pinfunction "1_1") (pintype "passive"))
      (node (ref "C8") (pin "2") (pinfunction "2_2") (pintype "passive"))
      (node (ref "C9") (pin "2") (pinfunction "2_2") (pintype "passive"))
      (node (ref "D1") (pin "A") (pinfunction "A_A") (pintype "passive"))
      (node (ref "D2") (pin "A") (pinfunction "A_A") (pintype "passive"))
      (node (ref "D3") (pin "A") (pinfunction "A_A") (pintype "passive"))
      (node (ref "D4") (pin "1") (pinfunction "K2_1") (pintype "passive"))
      (node (ref "D5") (pin "1") (pinfunction "K2_1") (pintype "passive"))
      (node (ref "D6") (pin "1") (pinfunction "K2_1") (pintype "passive"))
      (node (ref "D7") (pin "1") (pinfunction "K2_1") (pintype "passive"))
      (node (ref "D8") (pin "1") (pinfunction "K2_1") (pintype "passive"))
      (node (ref "J1") (pin "5") (pinfunction "5_5") (pintype "passive"))
      (node (ref "J1") (pin "7") (pinfunction "7_7") (pintype "passive"))
      (node (ref "J1") (pin "S1") (pinfunction "SHIELD1_S1") (pintype "passive"))
      (node (ref "J1") (pin "S2") (pinfunction "SHIELD1_S2") (pintype "passive"))
      (node (ref "J2") (pin "S2") (pinfunction "SHIELD2_S2") (pintype "passive"))
      (node (ref "J3") (pin "S2") (pinfunction "SHIELD2_S2") (pintype "passive"))
      (node (ref "J4") (pin "2") (pinfunction "2_2") (pintype "passive"))
      (node (ref "J4") (pin "S2") (pinfunction "SHIELD2_S2") (pintype "passive"))
      (node (ref "J5") (pin "2") (pinfunction "2_2") (pintype "passive"))
      (node (ref "J5") (pin "S2") (pinfunction "SHIELD2_S2") (pintype "passive"))
      (node (ref "J6") (pin "2") (pinfunction "2_2") (pintype "passive"))
      (node (ref "J6") (pin "S2") (pinfunction "SHIELD2_S2") (pintype "passive"))
      (node (ref "J7") (pin "S1") (pinfunction "SHIELD_S1") (pintype "passive"))
      (node (ref "J7") (pin "S2") (pinfunction "SHIELD_S2") (pintype "passive"))
      (node (ref "J8") (pin "S1") (pinfunction "SHIELD_S1") (pintype "passive"))
      (node (ref "J8") (pin "S2") (pinfunction "SHIELD_S2") (pintype "passive"))
      (node (ref "J9") (pin "3") (pinfunction "3_3") (pintype "passive"))
      (node (ref "J9") (pin "6") (pinfunction "6_6") (pintype "passive"))
      (node (ref "R19") (pin "1") (pinfunction "1_1") (pintype "passive"))
      (node (ref "R20") (pin "2") (pinfunction "2_2") (pintype "passive"))
      (node (ref "R22") (pin "1") (pinfunction "1_1") (pintype "passive"))
      (node (ref "R23") (pin "2") (pinfunction "2_2") (pintype "passive"))
      (node (ref "U1") (pin "U1") (pinfunction "GND_U1") (pintype "power_in"))
      (node (ref "U2") (pin "U1") (pinfunction "GND_U1") (pintype "power_in"))
      (node (ref "U3") (pin "12") (pinfunction "VSSA_12") (pintype "power_in"))
      (node (ref "U3") (pin "18") (pinfunction "VSS_18") (pintype "power_in"))
      (node (ref "U3") (pin "60") (pinfunction "BOOT0_60") (pintype "input"))
      (node (ref "U3") (pin "63") (pinfunction "VSS_63") (pintype "power_in"))
      (node (ref "U4") (pin "4") (pinfunction "GND_4") (pintype "power_in"))
      (node (ref "U5") (pin "2") (pinfunction "GND_2") (pintype "power_in"))
      (node (ref "U5") (pin "5") (pinfunction "VIN-_5") (pintype "input"))
      (node (ref "U6") (pin "2") (pinfunction "GND_2") (pintype "power_in"))
      (node (ref "U6") (pin "5") (pinfunction "VIN-_5") (pintype "input"))
      (node (ref "Y1") (pin "1") (pinfunction "NC_1") (pintype "passive"))
      (node (ref "Y1") (pin "2") (pinfunction "GND_2") (pintype "power_in"))
    )
    (net (code "34") (name "Net-(D4-A2)") (class "Default")
      (node (ref "D4") (pin "2") (pinfunction "A2_2") (pintype "passive"))
      (node (ref "R12") (pin "2") (pinfunction "2_2") (pintype "passive"))
    )
    (net (code "35") (name "Net-(D5-A2)") (class "Default")
      (node (ref "D5") (pin "2") (pinfunction "A2_2") (pintype "passive"))
      (node (ref "R13") (pin "2") (pinfunction "2_2") (pintype "passive"))
    )
    (net (code "36") (name "Net-(D6-A2)") (class "Default")
      (node (ref "D6") (pin "2") (pinfunction "A2_2") (pintype "passive"))
      (node (ref "R14") (pin "2") (pinfunction "2_2") (pintype "passive"))
    )
    (net (code "37") (name "Net-(D7-A2)") (class "Default")
      (node (ref "D7") (pin "2") (pinfunction "A2_2") (pintype "passive"))
      (node (ref "R15") (pin "2") (pinfunction "2_2") (pintype "passive"))
    )
    (net (code "38") (name "Net-(D8-A2)") (class "Default")
      (node (ref "D8") (pin "2") (pinfunction "A2_2") (pintype "passive"))
      (node (ref "R16") (pin "2") (pinfunction "2_2") (pintype "passive"))
    )
    (net (code "39") (name "Net-(U3B-VCAP_1)") (class "Default")
      (node (ref "C15") (pin "2") (pinfunction "2_2") (pintype "passive"))
      (node (ref "U3") (pin "31") (pinfunction "VCAP_1_31") (pintype "power_in"))
    )
    (net (code "40") (name "Net-(U3B-VCAP_2)") (class "Default")
      (node (ref "C14") (pin "1") (pinfunction "1_1") (pintype "passive"))
      (node (ref "U3") (pin "47") (pinfunction "VCAP_2_47") (pintype "power_in"))
    )
    (net (code "41") (name "Net-(U4-D)") (class "Default")
      (node (ref "R3") (pin "2") (pintype "passive"))
      (node (ref "U4") (pin "3") (pinfunction "D_3") (pintype "input"))
    )
    (net (code "42") (name "Net-(U4-R)") (class "Default")
      (node (ref "R1") (pin "1") (pinfunction "1_1") (pintype "passive"))
      (node (ref "R2") (pin "2") (pintype "passive"))
      (node (ref "U4") (pin "2") (pinfunction "R_2") (pintype "output"))
    )
    (net (code "43") (name "Net-(U5-OUT)") (class "Default")
      (node (ref "R18") (pin "1") (pinfunction "1_1") (pintype "passive"))
      (node (ref "U5") (pin "6") (pinfunction "OUT_6") (pintype "output"))
    )
    (net (code "44") (name "Net-(U5-REF)") (class "Default")
      (node (ref "C9") (pin "1") (pinfunction "1_1") (pintype "passive"))
      (node (ref "U5") (pin "1") (pinfunction "REF_1") (pintype "input"))
    )
    (net (code "45") (name "Net-(U6-OUT)") (class "Default")
      (node (ref "R21") (pin "1") (pinfunction "1_1") (pintype "passive"))
      (node (ref "U6") (pin "6") (pinfunction "OUT_6") (pintype "output"))
    )
    (net (code "46") (name "Net-(U6-REF)") (class "Default")
      (node (ref "C12") (pin "1") (pinfunction "1_1") (pintype "passive"))
      (node (ref "U6") (pin "1") (pinfunction "REF_1") (pintype "input"))
    )
    (net (code "47") (name "Net-(Y1-OUT)") (class "Default")
      (node (ref "R5") (pin "2") (pinfunction "2_2") (pintype "passive"))
      (node (ref "Y1") (pin "3") (pinfunction "OUT_3") (pintype "output"))
    )
    (net (code "48") (name "Net-(Y1-VDD)") (class "Default")
      (node (ref "C6") (pin "2") (pinfunction "2_2") (pintype "passive"))
      (node (ref "C7") (pin "2") (pinfunction "2_2") (pintype "passive"))
      (node (ref "R6") (pin "1") (pinfunction "1_1") (pintype "passive"))
      (node (ref "Y1") (pin "4") (pinfunction "VDD_4") (pintype "power_in"))
    )
    (net (code "49") (name "unconnected-(J2-SHIELD1-PadS1)") (class "Default")
      (node (ref "J2") (pin "S1") (pinfunction "SHIELD1_S1") (pintype "passive"))
    )
    (net (code "50") (name "unconnected-(J3-SHIELD1-PadS1)") (class "Default")
      (node (ref "J3") (pin "S1") (pinfunction "SHIELD1_S1") (pintype "passive"))
    )
    (net (code "51") (name "unconnected-(J4-SHIELD1-PadS1)") (class "Default")
      (node (ref "J4") (pin "S1") (pinfunction "SHIELD1_S1") (pintype "passive"))
    )
    (net (code "52") (name "unconnected-(J5-SHIELD1-PadS1)") (class "Default")
      (node (ref "J5") (pin "S1") (pinfunction "SHIELD1_S1") (pintype "passive"))
    )
    (net (code "53") (name "unconnected-(J6-SHIELD1-PadS1)") (class "Default")
      (node (ref "J6") (pin "S1") (pinfunction "SHIELD1_S1") (pintype "passive"))
    )
    (net (code "54") (name "unconnected-(J9-Pad1)") (class "Default")
      (node (ref "J9") (pin "1") (pinfunction "1_1") (pintype "passive+no_connect"))
    )
    (net (code "55") (name "unconnected-(J9-Pad9)") (class "Default")
      (node (ref "J9") (pin "9") (pinfunction "9_9") (pintype "passive+no_connect"))
    )
    (net (code "56") (name "unconnected-(J9-Pad11)") (class "Default")
      (node (ref "J9") (pin "11") (pinfunction "11_11") (pintype "passive+no_connect"))
    )
    (net (code "57") (name "unconnected-(U1-DNC-PadU8)") (class "Default")
      (node (ref "U1") (pin "U8") (pinfunction "DNC_U8") (pintype "passive+no_connect"))
    )
    (net (code "58") (name "unconnected-(U2-DNC-PadU8)") (class "Default")
      (node (ref "U2") (pin "U8") (pinfunction "DNC_U8") (pintype "passive+no_connect"))
    )
    (net (code "59") (name "unconnected-(U3B-PA0_WKUP-Pad14)") (class "Default")
      (node (ref "U3") (pin "14") (pinfunction "PA0_WKUP_14") (pintype "bidirectional"))
    )
    (net (code "60") (name "unconnected-(U3B-PA1-Pad15)") (class "Default")
      (node (ref "U3") (pin "15") (pinfunction "PA1_15") (pintype "bidirectional"))
    )
    (net (code "61") (name "unconnected-(U3B-PA3-Pad17)") (class "Default")
      (node (ref "U3") (pin "17") (pinfunction "PA3_17") (pintype "bidirectional"))
    )
    (net (code "62") (name "unconnected-(U3B-PA4-Pad20)") (class "Default")
      (node (ref "U3") (pin "20") (pinfunction "PA4_20") (pintype "bidirectional"))
    )
    (net (code "63") (name "unconnected-(U3B-PA8-Pad41)") (class "Default")
      (node (ref "U3") (pin "41") (pinfunction "PA8_41") (pintype "bidirectional"))
    )
    (net (code "64") (name "unconnected-(U3B-PA11-Pad44)") (class "Default")
      (node (ref "U3") (pin "44") (pinfunction "PA11_44") (pintype "bidirectional"))
    )
    (net (code "65") (name "unconnected-(U3B-PA12-Pad45)") (class "Default")
      (node (ref "U3") (pin "45") (pinfunction "PA12_45") (pintype "bidirectional"))
    )
    (net (code "66") (name "unconnected-(U3B-PA15-Pad50)") (class "Default")
      (node (ref "U3") (pin "50") (pinfunction "PA15_50") (pintype "bidirectional"))
    )
    (net (code "67") (name "unconnected-(U3B-PB0-Pad26)") (class "Default")
      (node (ref "U3") (pin "26") (pinfunction "PB0_26") (pintype "bidirectional"))
    )
    (net (code "68") (name "unconnected-(U3B-PB1-Pad27)") (class "Default")
      (node (ref "U3") (pin "27") (pinfunction "PB1_27") (pintype "bidirectional"))
    )
    (net (code "69") (name "unconnected-(U3B-PB2-Pad28)") (class "Default")
      (node (ref "U3") (pin "28") (pinfunction "PB2_28") (pintype "bidirectional"))
    )
    (net (code "70") (name "unconnected-(U3B-PB4-Pad56)") (class "Default")
      (node (ref "U3") (pin "56") (pinfunction "PB4_56") (pintype "bidirectional"))
    )
    (net (code "71") (name "unconnected-(U3B-PB5-Pad57)") (class "Default")
      (node (ref "U3") (pin "57") (pinfunction "PB5_57") (pintype "bidirectional"))
    )
    (net (code "72") (name "unconnected-(U3B-PB6-Pad58)") (class "Default")
      (node (ref "U3") (pin "58") (pinfunction "PB6_58") (pintype "bidirectional"))
    )
    (net (code "73") (name "unconnected-(U3B-PB7-Pad59)") (class "Default")
      (node (ref "U3") (pin "59") (pinfunction "PB7_59") (pintype "bidirectional"))
    )
    (net (code "74") (name "unconnected-(U3B-PB8-Pad61)") (class "Default")
      (node (ref "U3") (pin "61") (pinfunction "PB8_61") (pintype "bidirectional"))
    )
    (net (code "75") (name "unconnected-(U3B-PB9-Pad62)") (class "Default")
      (node (ref "U3") (pin "62") (pinfunction "PB9_62") (pintype "bidirectional"))
    )
    (net (code "76") (name "unconnected-(U3B-PB12-Pad33)") (class "Default")
      (node (ref "U3") (pin "33") (pinfunction "PB12_33") (pintype "bidirectional"))
    )
    (net (code "77") (name "unconnected-(U3B-PC0-Pad8)") (class "Default")
      (node (ref "U3") (pin "8") (pinfunction "PC0_8") (pintype "bidirectional"))
    )
    (net (code "78") (name "unconnected-(U3B-PC1-Pad9)") (class "Default")
      (node (ref "U3") (pin "9") (pinfunction "PC1_9") (pintype "bidirectional"))
    )
    (net (code "79") (name "unconnected-(U3B-PC2-Pad10)") (class "Default")
      (node (ref "U3") (pin "10") (pinfunction "PC2_10") (pintype "bidirectional"))
    )
    (net (code "80") (name "unconnected-(U3B-PC3-Pad11)") (class "Default")
      (node (ref "U3") (pin "11") (pinfunction "PC3_11") (pintype "bidirectional"))
    )
    (net (code "81") (name "unconnected-(U3B-PC4-Pad24)") (class "Default")
      (node (ref "U3") (pin "24") (pinfunction "PC4_24") (pintype "bidirectional"))
    )
    (net (code "82") (name "unconnected-(U3B-PC6-Pad37)") (class "Default")
      (node (ref "U3") (pin "37") (pinfunction "PC6_37") (pintype "bidirectional"))
    )
    (net (code "83") (name "unconnected-(U3B-PC7-Pad38)") (class "Default")
      (node (ref "U3") (pin "38") (pinfunction "PC7_38") (pintype "bidirectional"))
    )
    (net (code "84") (name "unconnected-(U3B-PC8-Pad39)") (class "Default")
      (node (ref "U3") (pin "39") (pinfunction "PC8_39") (pintype "bidirectional"))
    )
    (net (code "85") (name "unconnected-(U3B-PC9-Pad40)") (class "Default")
      (node (ref "U3") (pin "40") (pinfunction "PC9_40") (pintype "bidirectional"))
    )
    (net (code "86") (name "unconnected-(U3B-PC10-Pad51)") (class "Default")
      (node (ref "U3") (pin "51") (pinfunction "PC10_51") (pintype "bidirectional"))
    )
    (net (code "87") (name "unconnected-(U3B-PC11-Pad52)") (class "Default")
      (node (ref "U3") (pin "52") (pinfunction "PC11_52") (pintype "bidirectional"))
    )
    (net (code "88") (name "unconnected-(U3B-PC12-Pad53)") (class "Default")
      (node (ref "U3") (pin "53") (pinfunction "PC12_53") (pintype "bidirectional"))
    )
    (net (code "89") (name "unconnected-(U3B-PC13-Pad2)") (class "Default")
      (node (ref "U3") (pin "2") (pinfunction "PC13_2") (pintype "bidirectional"))
    )
    (net (code "90") (name "unconnected-(U3B-PC14{slash}OSC32_IN-Pad3)") (class "Default")
      (node (ref "U3") (pin "3") (pinfunction "PC14/OSC32_IN_3") (pintype "bidirectional"))
    )
    (net (code "91") (name "unconnected-(U3B-PC15{slash}OSC32_OUT-Pad4)") (class "Default")
      (node (ref "U3") (pin "4") (pinfunction "PC15/OSC32_OUT_4") (pintype "bidirectional"))
    )
    (net (code "92") (name "unconnected-(U3B-PD2-Pad54)") (class "Default")
      (node (ref "U3") (pin "54") (pinfunction "PD2_54") (pintype "bidirectional"))
    )
    (net (code "93") (name "unconnected-(U3B-PH1{slash}OSC_OUT-Pad6)") (class "Default")
      (node (ref "U3") (pin "6") (pinfunction "PH1/OSC_OUT_6") (pintype "bidirectional+no_connect"))
    )
  )
)
